# m5stack-rfm95.net
KiCad netlist of a schematic drawn in EAGLE
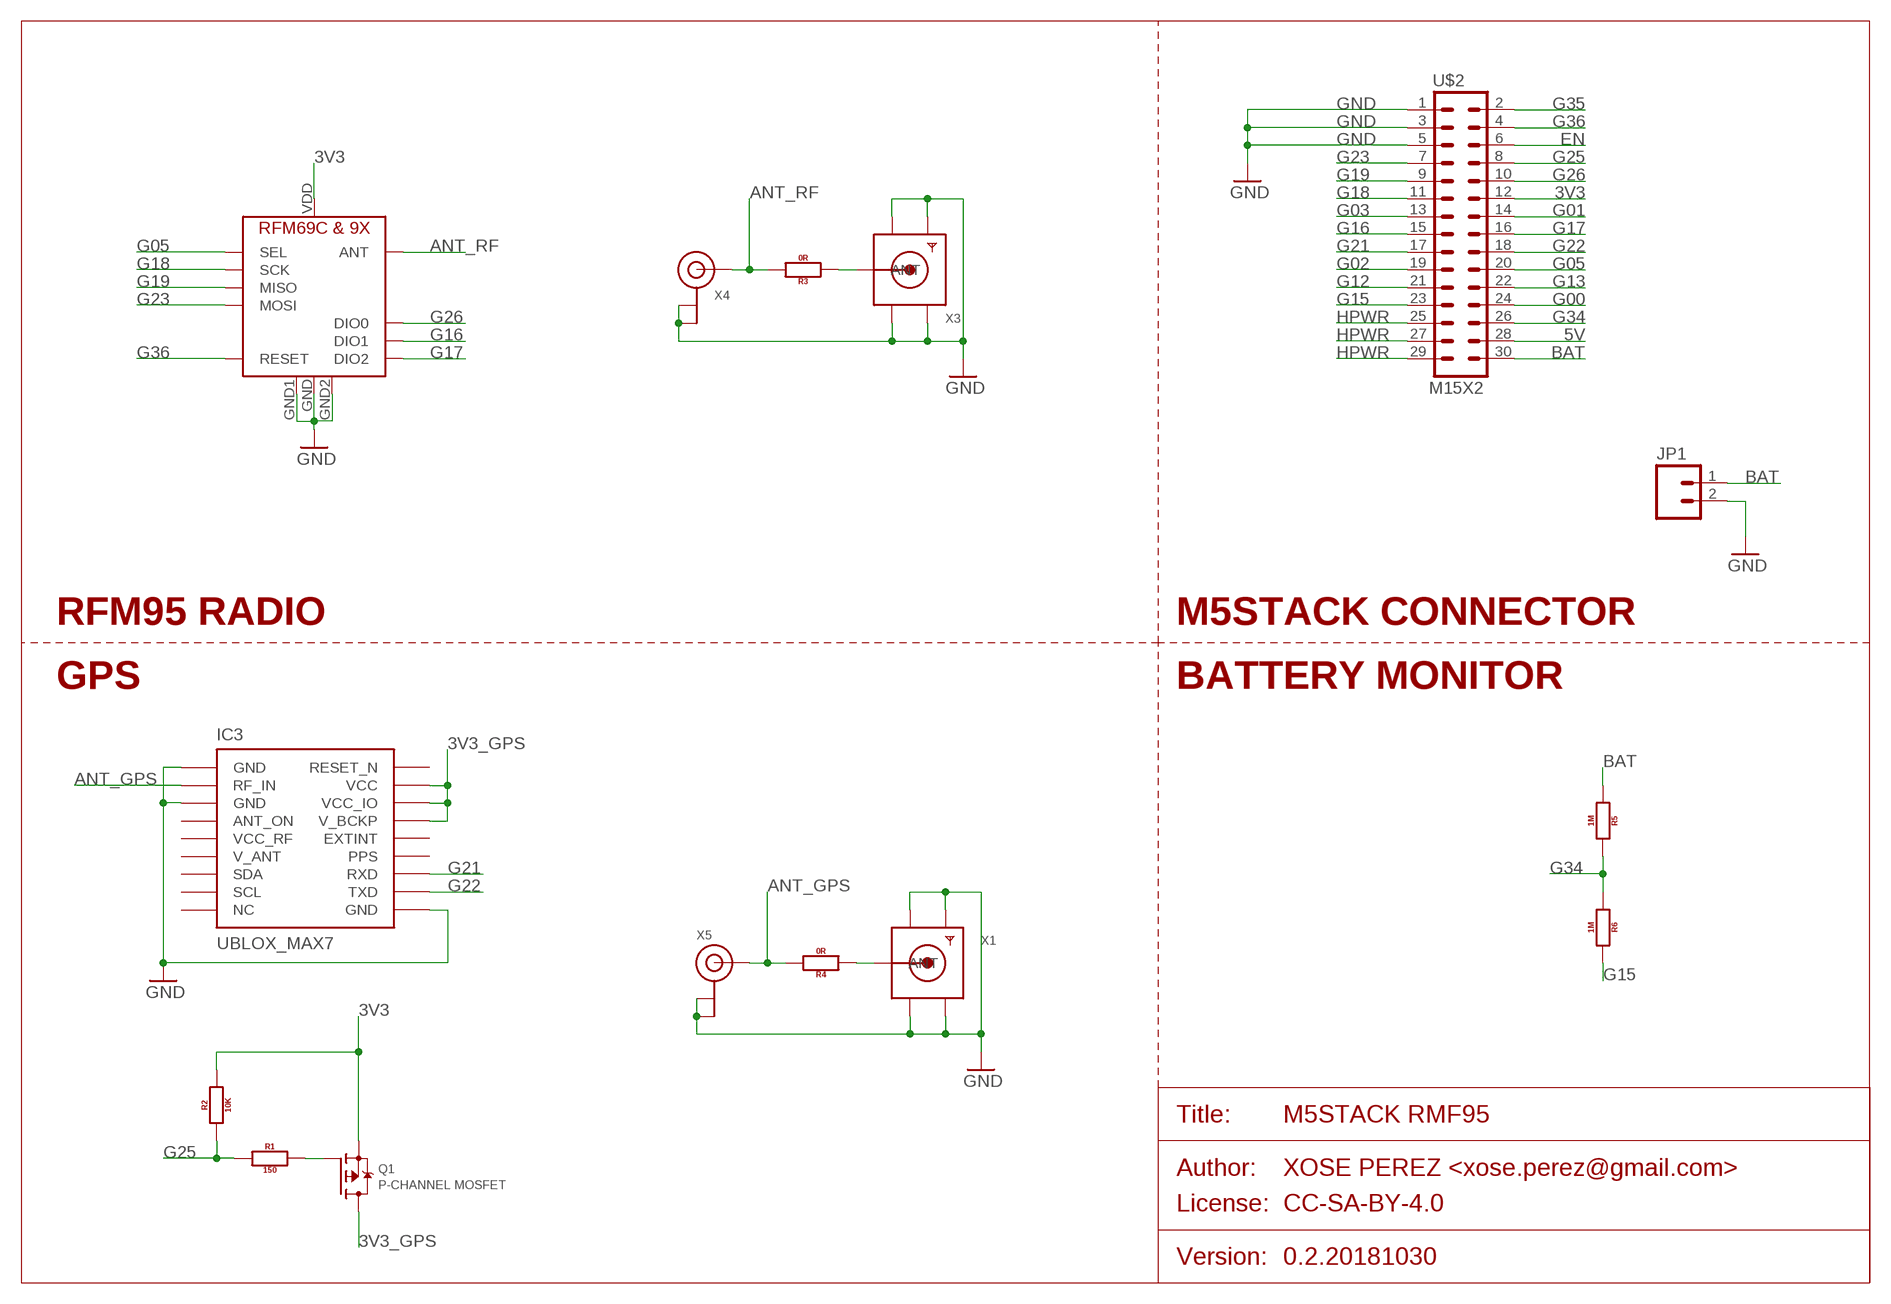
[diagram p0: schematic, sheet 1]

(export (version "E")
  (design (tool "Eeschema 10.0.6"))
  (components
    (comp (ref "IC1")
      (value "RFM69HCW-RFM95")
      (footprint "eagle-import:RFM69HCW-RFM95-MINPADS")
      (libsource (lib "eagle-import") (part "RFM69HCW-RFM95"))
    )
    (comp (ref "IC3")
      (value "UBLOX_MAX7")
      (footprint "eagle-import:UBLOX_MAX7")
      (libsource (lib "eagle-import") (part "UBLOX_MAX7"))
    )
    (comp (ref "JP1")
      (value "M02-JST-2MM-SMT")
      (footprint "eagle-import:JST-2-SMD")
      (libsource (lib "eagle-import") (part "M02-JST-2MM-SMT"))
    )
    (comp (ref "Q1")
      (value "P-CHANNEL MOSFET")
      (footprint "eagle-import:SOT23-R")
      (libsource (lib "eagle-import") (part "MOSFET-P"))
    )
    (comp (ref "R1")
      (value "150")
      (footprint "eagle-import:0805")
      (libsource (lib "eagle-import") (part "RESISTOR0805"))
    )
    (comp (ref "R2")
      (value "10K")
      (footprint "eagle-import:0805")
      (libsource (lib "eagle-import") (part "RESISTOR0805"))
    )
    (comp (ref "R3")
      (value "0R")
      (footprint "eagle-import:0805")
      (libsource (lib "eagle-import") (part "RESISTOR0805"))
    )
    (comp (ref "R4")
      (value "0R")
      (footprint "eagle-import:0805")
      (libsource (lib "eagle-import") (part "RESISTOR0805"))
    )
    (comp (ref "R5")
      (value "1M")
      (footprint "eagle-import:0805")
      (libsource (lib "eagle-import") (part "RESISTOR0805"))
    )
    (comp (ref "R6")
      (value "1M")
      (footprint "eagle-import:0805")
      (libsource (lib "eagle-import") (part "RESISTOR0805"))
    )
    (comp (ref "U$2")
      (value "M15X2")
      (footprint "eagle-import:2X15")
      (libsource (lib "eagle-import") (part "M15X2"))
    )
    (comp (ref "X1")
      (value "SMACONNECTOR")
      (footprint "eagle-import:SMA90_DIP")
      (libsource (lib "eagle-import") (part "SMACONNECTOR"))
    )
    (comp (ref "X3")
      (value "SMACONNECTOR")
      (footprint "eagle-import:SMA90_DIP")
      (libsource (lib "eagle-import") (part "SMACONNECTOR"))
    )
    (comp (ref "X4")
      (value "ANTENNA_U.FL")
      (footprint "eagle-import:U.FL")
      (libsource (lib "eagle-import") (part "ANTENNA_U.FL"))
    )
    (comp (ref "X5")
      (value "ANTENNA_U.FL")
      (footprint "eagle-import:U.FL")
      (libsource (lib "eagle-import") (part "ANTENNA_U.FL"))
    )
  )
  (nets
    (net (code "1") (name "/3V3") (class "Default")
      (node (ref "IC1") (pin "VDD") (pinfunction "VCC_VDD") (pintype "power_in"))
      (node (ref "Q1") (pin "2") (pinfunction "S_2") (pintype "passive"))
      (node (ref "R2") (pin "2") (pinfunction "2_2") (pintype "passive"))
      (node (ref "U$2") (pin "12") (pinfunction "12_12") (pintype "passive"))
    )
    (net (code "2") (name "/3V3_GPS") (class "Default")
      (node (ref "IC3") (pin "P$6") (pinfunction "V_BCKP_P$6") (pintype "power_in"))
      (node (ref "IC3") (pin "P$7") (pinfunction "VCC_IO_P$7") (pintype "power_in"))
      (node (ref "IC3") (pin "P$8") (pinfunction "VCC_P$8") (pintype "power_in"))
      (node (ref "Q1") (pin "3") (pinfunction "D_3") (pintype "passive"))
    )
    (net (code "3") (name "/5V") (class "Default")
      (node (ref "U$2") (pin "28") (pinfunction "28_28") (pintype "passive"))
    )
    (net (code "4") (name "/ANT_GPS") (class "Default")
      (node (ref "IC3") (pin "P$11") (pinfunction "RF_IN_P$11") (pintype "input"))
      (node (ref "R4") (pin "2") (pinfunction "2_2") (pintype "passive"))
      (node (ref "X5") (pin "3") (pinfunction "SIGNAL_3") (pintype "passive"))
    )
    (net (code "5") (name "/ANT_RF") (class "Default")
      (node (ref "IC1") (pin "ANT") (pinfunction "ANT_ANT") (pintype "passive"))
      (node (ref "R3") (pin "2") (pinfunction "2_2") (pintype "passive"))
      (node (ref "X4") (pin "3") (pinfunction "SIGNAL_3") (pintype "passive"))
    )
    (net (code "6") (name "/BAT") (class "Default")
      (node (ref "JP1") (pin "1") (pinfunction "2_1") (pintype "passive"))
      (node (ref "R5") (pin "1") (pinfunction "1_1") (pintype "passive"))
      (node (ref "U$2") (pin "30") (pinfunction "30_30") (pintype "passive"))
    )
    (net (code "7") (name "/EN") (class "Default")
      (node (ref "U$2") (pin "6") (pinfunction "6_6") (pintype "passive"))
    )
    (net (code "8") (name "/G00") (class "Default")
      (node (ref "U$2") (pin "24") (pinfunction "24_24") (pintype "passive"))
    )
    (net (code "9") (name "/G01") (class "Default")
      (node (ref "U$2") (pin "14") (pinfunction "14_14") (pintype "passive"))
    )
    (net (code "10") (name "/G02") (class "Default")
      (node (ref "U$2") (pin "19") (pinfunction "19_19") (pintype "passive"))
    )
    (net (code "11") (name "/G03") (class "Default")
      (node (ref "U$2") (pin "13") (pinfunction "13_13") (pintype "passive"))
    )
    (net (code "12") (name "/G05") (class "Default")
      (node (ref "IC1") (pin "NSS") (pinfunction "SEL_NSS") (pintype "input"))
      (node (ref "U$2") (pin "20") (pinfunction "20_20") (pintype "passive"))
    )
    (net (code "13") (name "/G12") (class "Default")
      (node (ref "U$2") (pin "21") (pinfunction "21_21") (pintype "passive"))
    )
    (net (code "14") (name "/G13") (class "Default")
      (node (ref "U$2") (pin "22") (pinfunction "22_22") (pintype "passive"))
    )
    (net (code "15") (name "/G15") (class "Default")
      (node (ref "R6") (pin "2") (pinfunction "2_2") (pintype "passive"))
      (node (ref "U$2") (pin "23") (pinfunction "23_23") (pintype "passive"))
    )
    (net (code "16") (name "/G16") (class "Default")
      (node (ref "IC1") (pin "DIO1") (pinfunction "DIO1_DIO1") (pintype "bidirectional"))
      (node (ref "U$2") (pin "15") (pinfunction "15_15") (pintype "passive"))
    )
    (net (code "17") (name "/G17") (class "Default")
      (node (ref "IC1") (pin "DIO2") (pinfunction "DIO2_DIO2") (pintype "bidirectional"))
      (node (ref "U$2") (pin "16") (pinfunction "16_16") (pintype "passive"))
    )
    (net (code "18") (name "/G18") (class "Default")
      (node (ref "IC1") (pin "SCK") (pinfunction "SCK_SCK") (pintype "input"))
      (node (ref "U$2") (pin "11") (pinfunction "11_11") (pintype "passive"))
    )
    (net (code "19") (name "/G19") (class "Default")
      (node (ref "IC1") (pin "MISO") (pinfunction "MISO_MISO") (pintype "output"))
      (node (ref "U$2") (pin "9") (pinfunction "9_9") (pintype "passive"))
    )
    (net (code "20") (name "/G21") (class "Default")
      (node (ref "IC3") (pin "P$3") (pinfunction "RXD_P$3") (pintype "bidirectional"))
      (node (ref "U$2") (pin "17") (pinfunction "17_17") (pintype "passive"))
    )
    (net (code "21") (name "/G22") (class "Default")
      (node (ref "IC3") (pin "P$2") (pinfunction "TXD_P$2") (pintype "output"))
      (node (ref "U$2") (pin "18") (pinfunction "18_18") (pintype "passive"))
    )
    (net (code "22") (name "/G23") (class "Default")
      (node (ref "IC1") (pin "MOSI") (pinfunction "MOSI_MOSI") (pintype "input"))
      (node (ref "U$2") (pin "7") (pinfunction "7_7") (pintype "passive"))
    )
    (net (code "23") (name "/G25") (class "Default")
      (node (ref "R1") (pin "1") (pinfunction "1_1") (pintype "passive"))
      (node (ref "R2") (pin "1") (pinfunction "1_1") (pintype "passive"))
      (node (ref "U$2") (pin "8") (pinfunction "8_8") (pintype "passive"))
    )
    (net (code "24") (name "/G26") (class "Default")
      (node (ref "IC1") (pin "DIO0") (pinfunction "DIO0_DIO0") (pintype "bidirectional"))
      (node (ref "U$2") (pin "10") (pinfunction "10_10") (pintype "passive"))
    )
    (net (code "25") (name "/G34") (class "Default")
      (node (ref "R5") (pin "2") (pinfunction "2_2") (pintype "passive"))
      (node (ref "R6") (pin "1") (pinfunction "1_1") (pintype "passive"))
      (node (ref "U$2") (pin "26") (pinfunction "26_26") (pintype "passive"))
    )
    (net (code "26") (name "/G35") (class "Default")
      (node (ref "U$2") (pin "2") (pinfunction "2_2") (pintype "passive"))
    )
    (net (code "27") (name "/G36") (class "Default")
      (node (ref "IC1") (pin "RESET") (pinfunction "RESET_RESET") (pintype "input"))
      (node (ref "U$2") (pin "4") (pinfunction "4_4") (pintype "passive"))
    )
    (net (code "28") (name "/HPWR") (class "Default")
      (node (ref "U$2") (pin "25") (pinfunction "25_25") (pintype "passive"))
      (node (ref "U$2") (pin "27") (pinfunction "27_27") (pintype "passive"))
      (node (ref "U$2") (pin "29") (pinfunction "29_29") (pintype "passive"))
    )
    (net (code "29") (name "/VCC_RF") (class "Default")
      (node (ref "IC3") (pin "P$14") (pinfunction "VCC_RF_P$14") (pintype "power_in"))
    )
    (net (code "30") (name "/V_ANT") (class "Default")
      (node (ref "IC3") (pin "P$15") (pinfunction "V_ANT_P$15") (pintype "power_in"))
    )
    (net (code "31") (name "GND") (class "Default")
      (node (ref "IC1") (pin "GND") (pinfunction "GND_GND") (pintype "power_in"))
      (node (ref "IC1") (pin "GND1") (pinfunction "GND1_GND1") (pintype "power_in"))
      (node (ref "IC1") (pin "GND2") (pinfunction "GND2_GND2") (pintype "power_in"))
      (node (ref "IC3") (pin "P$1") (pinfunction "GND_P$1") (pintype "power_in"))
      (node (ref "IC3") (pin "P$10") (pinfunction "GND_P$10") (pintype "power_in"))
      (node (ref "IC3") (pin "P$12") (pinfunction "GND_P$12") (pintype "power_in"))
      (node (ref "JP1") (pin "2") (pinfunction "1_2") (pintype "passive"))
      (node (ref "U$2") (pin "1") (pinfunction "1_1") (pintype "passive"))
      (node (ref "U$2") (pin "3") (pinfunction "3_3") (pintype "passive"))
      (node (ref "U$2") (pin "5") (pinfunction "5_5") (pintype "passive"))
      (node (ref "X1") (pin "GND1") (pinfunction "GND1_GND1") (pintype "power_in"))
      (node (ref "X1") (pin "GND2") (pinfunction "GND2_GND2") (pintype "power_in"))
      (node (ref "X1") (pin "GND3") (pinfunction "GND3_GND3") (pintype "power_in"))
      (node (ref "X1") (pin "GND4") (pinfunction "GND4_GND4") (pintype "power_in"))
      (node (ref "X3") (pin "GND1") (pinfunction "GND1_GND1") (pintype "power_in"))
      (node (ref "X3") (pin "GND2") (pinfunction "GND2_GND2") (pintype "power_in"))
      (node (ref "X3") (pin "GND3") (pinfunction "GND3_GND3") (pintype "power_in"))
      (node (ref "X3") (pin "GND4") (pinfunction "GND4_GND4") (pintype "power_in"))
      (node (ref "X4") (pin "1") (pinfunction "GND_1") (pintype "passive"))
      (node (ref "X4") (pin "2") (pinfunction "GND_2") (pintype "passive"))
      (node (ref "X5") (pin "1") (pinfunction "GND_1") (pintype "passive"))
      (node (ref "X5") (pin "2") (pinfunction "GND_2") (pintype "passive"))
    )
    (net (code "32") (name "Net-(Q1-G)") (class "Default")
      (node (ref "Q1") (pin "1") (pinfunction "G_1") (pintype "passive"))
      (node (ref "R1") (pin "2") (pinfunction "2_2") (pintype "passive"))
    )
    (net (code "33") (name "Net-(X1-ANT)") (class "Default")
      (node (ref "R4") (pin "1") (pinfunction "1_1") (pintype "passive"))
      (node (ref "X1") (pin "ANTENNA") (pinfunction "ANT_ANTENNA") (pintype "bidirectional"))
    )
    (net (code "34") (name "Net-(X3-ANT)") (class "Default")
      (node (ref "R3") (pin "1") (pinfunction "1_1") (pintype "passive"))
      (node (ref "X3") (pin "ANTENNA") (pinfunction "ANT_ANTENNA") (pintype "bidirectional"))
    )
    (net (code "35") (name "unconnected-(IC3-ANT_ON-PadP$13)") (class "Default")
      (node (ref "IC3") (pin "P$13") (pinfunction "ANT_ON_P$13") (pintype "output"))
    )
    (net (code "36") (name "unconnected-(IC3-EXTINT-PadP$5)") (class "Default")
      (node (ref "IC3") (pin "P$5") (pinfunction "EXTINT_P$5") (pintype "input"))
    )
    (net (code "37") (name "unconnected-(IC3-NC-PadP$18)") (class "Default")
      (node (ref "IC3") (pin "P$18") (pinfunction "NC_P$18") (pintype "no_connect"))
    )
    (net (code "38") (name "unconnected-(IC3-PPS-PadP$4)") (class "Default")
      (node (ref "IC3") (pin "P$4") (pinfunction "PPS_P$4") (pintype "output"))
    )
    (net (code "39") (name "unconnected-(IC3-RESET_N-PadP$9)") (class "Default")
      (node (ref "IC3") (pin "P$9") (pinfunction "RESET_N_P$9") (pintype "input"))
    )
    (net (code "40") (name "unconnected-(IC3-SCL-PadP$17)") (class "Default")
      (node (ref "IC3") (pin "P$17") (pinfunction "SCL_P$17") (pintype "bidirectional"))
    )
    (net (code "41") (name "unconnected-(IC3-SDA-PadP$16)") (class "Default")
      (node (ref "IC3") (pin "P$16") (pinfunction "SDA_P$16") (pintype "bidirectional"))
    )
  )
)
